# flash.net
KiCad netlist of a schematic drawn in Altium Designer
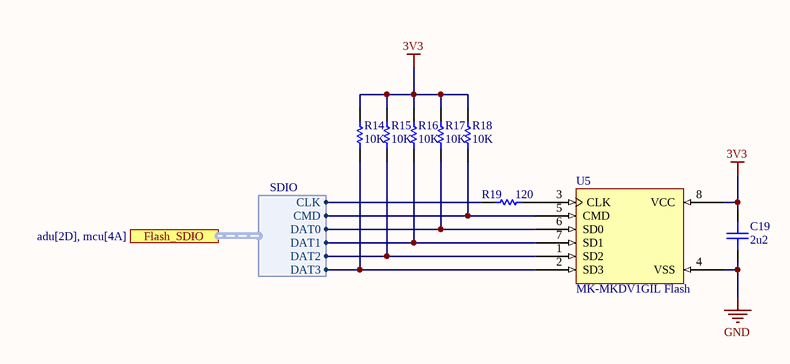
[diagram p0: flash.SchDoc]

(export (version "E")
  (design (tool "Eeschema 10.0.6"))
  (components
    (comp (ref "C19")
      (value "2u2")
      (footprint "CAP-0603-NP")
      (description "Capacitor")
      (libsource (lib "drfc_schlib") (part "Capacitor"))
    )
    (comp (ref "R14")
      (value "10K")
      (footprint "RES-0603")
      (description "Resistor")
      (libsource (lib "drfc_schlib") (part "Resistor"))
    )
    (comp (ref "R15")
      (value "10K")
      (footprint "RES-0603")
      (description "Resistor")
      (libsource (lib "drfc_schlib") (part "Resistor"))
    )
    (comp (ref "R16")
      (value "10K")
      (footprint "RES-0603")
      (description "Resistor")
      (libsource (lib "drfc_schlib") (part "Resistor"))
    )
    (comp (ref "R17")
      (value "10K")
      (footprint "RES-0603")
      (description "Resistor")
      (libsource (lib "drfc_schlib") (part "Resistor"))
    )
    (comp (ref "R18")
      (value "10K")
      (footprint "RES-0603")
      (description "Resistor")
      (libsource (lib "drfc_schlib") (part "Resistor"))
    )
    (comp (ref "R19")
      (value "120")
      (footprint "RES-0603")
      (description "Resistor")
      (libsource (lib "drfc_schlib") (part "Resistor"))
    )
    (comp (ref "U5")
      (value "MK-MKDV1GIL Flash")
      (footprint "QFN127P800X600X75-8N")
      (description "1Gbit LGA-8(6x8) SD NAND FLASH ROHS")
      (libsource (lib "drfc_schlib") (part "MK-MKDV1GIL"))
    )
  )
  (nets
    (net (code "2") (name "/CLK") (class "Default")
      (node (ref "R19") (pin "2") (pinfunction "2_2") (pintype "passive"))
    )
    (net (code "3") (name "/CMD") (class "Default")
      (node (ref "R18") (pin "1") (pinfunction "1_1") (pintype "passive"))
      (node (ref "U5") (pin "5") (pinfunction "CMD_5") (pintype "input"))
    )
    (net (code "4") (name "/DAT0") (class "Default")
      (node (ref "R17") (pin "1") (pinfunction "1_1") (pintype "passive"))
      (node (ref "U5") (pin "6") (pinfunction "SD0_6") (pintype "input"))
    )
    (net (code "5") (name "/DAT1") (class "Default")
      (node (ref "R16") (pin "1") (pinfunction "1_1") (pintype "passive"))
      (node (ref "U5") (pin "7") (pinfunction "SD1_7") (pintype "input"))
    )
    (net (code "6") (name "/DAT2") (class "Default")
      (node (ref "R15") (pin "1") (pinfunction "1_1") (pintype "passive"))
      (node (ref "U5") (pin "1") (pinfunction "SD2_1") (pintype "input"))
    )
    (net (code "7") (name "/DAT3") (class "Default")
      (node (ref "R14") (pin "1") (pinfunction "1_1") (pintype "passive"))
      (node (ref "U5") (pin "2") (pinfunction "SD3_2") (pintype "input"))
    )
    (net (code "9") (name "3V3") (class "Default")
      (node (ref "C19") (pin "2") (pinfunction "2_2") (pintype "passive"))
      (node (ref "R14") (pin "2") (pinfunction "2_2") (pintype "passive"))
      (node (ref "R15") (pin "2") (pinfunction "2_2") (pintype "passive"))
      (node (ref "R16") (pin "2") (pinfunction "2_2") (pintype "passive"))
      (node (ref "R17") (pin "2") (pinfunction "2_2") (pintype "passive"))
      (node (ref "R18") (pin "2") (pinfunction "2_2") (pintype "passive"))
      (node (ref "U5") (pin "8") (pinfunction "VCC_8") (pintype "input"))
    )
    (net (code "10") (name "GND") (class "Default")
      (node (ref "C19") (pin "1") (pinfunction "1_1") (pintype "passive"))
      (node (ref "U5") (pin "4") (pinfunction "VSS_4") (pintype "input"))
    )
    (net (code "11") (name "Net-(U5-CLK)") (class "Default")
      (node (ref "R19") (pin "1") (pinfunction "1_1") (pintype "passive"))
      (node (ref "U5") (pin "3") (pinfunction "CLK_3") (pintype "input"))
    )
  )
)
